# NBT_UIO_INT.net
KiCad netlist of a schematic drawn in Altium Designer
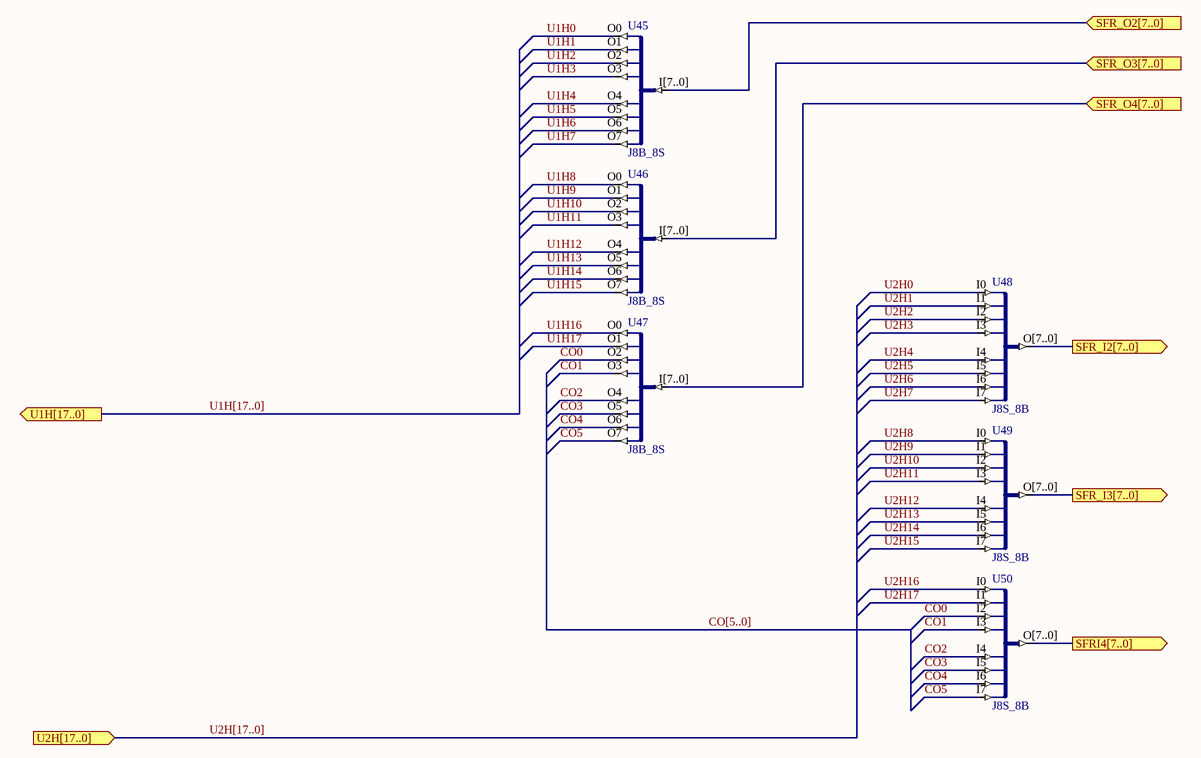
[diagram p0: NBT_UIO_INT.SCHDOC]

(export (version "E")
  (design (tool "Eeschema 10.0.6"))
  (components
    (comp (ref "U45")
      (value "J8B_8S")
      (description "8-Bit input bus to 8 single pin outputs")
      (fields (field (name "PUBLISHER") "Altium Limited"))
      (libsource (lib "FPGA Generic") (part "J8B_8S"))
    )
    (comp (ref "U46")
      (value "J8B_8S")
      (description "8-Bit input bus to 8 single pin outputs")
      (fields (field (name "PUBLISHER") "Altium Limited"))
      (libsource (lib "FPGA Generic") (part "J8B_8S"))
    )
    (comp (ref "U47")
      (value "J8B_8S")
      (description "8-Bit input bus to 8 single pin outputs")
      (fields (field (name "PUBLISHER") "Altium Limited"))
      (libsource (lib "FPGA Generic") (part "J8B_8S"))
    )
    (comp (ref "U48")
      (value "J8S_8B")
      (description "8 Single pin inputs to single 8-Bit output bus")
      (fields (field (name "PUBLISHER") "Altium Limited"))
      (libsource (lib "FPGA Generic") (part "J8S_8B"))
    )
    (comp (ref "U49")
      (value "J8S_8B")
      (description "8 Single pin inputs to single 8-Bit output bus")
      (fields (field (name "PUBLISHER") "Altium Limited"))
      (libsource (lib "FPGA Generic") (part "J8S_8B"))
    )
    (comp (ref "U50")
      (value "J8S_8B")
      (description "8 Single pin inputs to single 8-Bit output bus")
      (fields (field (name "PUBLISHER") "Altium Limited"))
      (libsource (lib "FPGA Generic") (part "J8S_8B"))
    )
  )
  (nets
    (net (code "49") (name "/CO0") (class "Default")
      (node (ref "U47") (pin "O2") (pinfunction "O2_O2") (pintype "output"))
      (node (ref "U50") (pin "I2") (pinfunction "I2_I2") (pintype "input"))
    )
    (net (code "50") (name "/CO1") (class "Default")
      (node (ref "U47") (pin "O3") (pinfunction "O3_O3") (pintype "output"))
      (node (ref "U50") (pin "I3") (pinfunction "I3_I3") (pintype "input"))
    )
    (net (code "51") (name "/CO2") (class "Default")
      (node (ref "U47") (pin "O4") (pinfunction "O4_O4") (pintype "output"))
      (node (ref "U50") (pin "I4") (pinfunction "I4_I4") (pintype "input"))
    )
    (net (code "52") (name "/CO3") (class "Default")
      (node (ref "U47") (pin "O5") (pinfunction "O5_O5") (pintype "output"))
      (node (ref "U50") (pin "I5") (pinfunction "I5_I5") (pintype "input"))
    )
    (net (code "53") (name "/CO4") (class "Default")
      (node (ref "U47") (pin "O6") (pinfunction "O6_O6") (pintype "output"))
      (node (ref "U50") (pin "I6") (pinfunction "I6_I6") (pintype "input"))
    )
    (net (code "54") (name "/CO5") (class "Default")
      (node (ref "U47") (pin "O7") (pinfunction "O7_O7") (pintype "output"))
      (node (ref "U50") (pin "I7") (pinfunction "I7_I7") (pintype "input"))
    )
    (net (code "56") (name "/SFRI4[7..0]") (class "Default")
      (node (ref "U50") (pin "O[7..0]") (pinfunction "O[7..0]_O[7..0]") (pintype "output"))
    )
    (net (code "57") (name "/SFR_I2[7..0]") (class "Default")
      (node (ref "U48") (pin "O[7..0]") (pinfunction "O[7..0]_O[7..0]") (pintype "output"))
    )
    (net (code "58") (name "/SFR_I3[7..0]") (class "Default")
      (node (ref "U49") (pin "O[7..0]") (pinfunction "O[7..0]_O[7..0]") (pintype "output"))
    )
    (net (code "59") (name "/SFR_O2[7..0]") (class "Default")
      (node (ref "U45") (pin "I[7..0]") (pinfunction "I[7..0]_I[7..0]") (pintype "input"))
    )
    (net (code "60") (name "/SFR_O3[7..0]") (class "Default")
      (node (ref "U46") (pin "I[7..0]") (pinfunction "I[7..0]_I[7..0]") (pintype "input"))
    )
    (net (code "61") (name "/SFR_O4[7..0]") (class "Default")
      (node (ref "U47") (pin "I[7..0]") (pinfunction "I[7..0]_I[7..0]") (pintype "input"))
    )
    (net (code "62") (name "/U1H0") (class "Default")
      (node (ref "U45") (pin "O0") (pinfunction "O0_O0") (pintype "output"))
    )
    (net (code "63") (name "/U1H1") (class "Default")
      (node (ref "U45") (pin "O1") (pinfunction "O1_O1") (pintype "output"))
    )
    (net (code "64") (name "/U1H2") (class "Default")
      (node (ref "U45") (pin "O2") (pinfunction "O2_O2") (pintype "output"))
    )
    (net (code "65") (name "/U1H3") (class "Default")
      (node (ref "U45") (pin "O3") (pinfunction "O3_O3") (pintype "output"))
    )
    (net (code "66") (name "/U1H4") (class "Default")
      (node (ref "U45") (pin "O4") (pinfunction "O4_O4") (pintype "output"))
    )
    (net (code "67") (name "/U1H5") (class "Default")
      (node (ref "U45") (pin "O5") (pinfunction "O5_O5") (pintype "output"))
    )
    (net (code "68") (name "/U1H6") (class "Default")
      (node (ref "U45") (pin "O6") (pinfunction "O6_O6") (pintype "output"))
    )
    (net (code "69") (name "/U1H7") (class "Default")
      (node (ref "U45") (pin "O7") (pinfunction "O7_O7") (pintype "output"))
    )
    (net (code "70") (name "/U1H8") (class "Default")
      (node (ref "U46") (pin "O0") (pinfunction "O0_O0") (pintype "output"))
    )
    (net (code "71") (name "/U1H9") (class "Default")
      (node (ref "U46") (pin "O1") (pinfunction "O1_O1") (pintype "output"))
    )
    (net (code "72") (name "/U1H10") (class "Default")
      (node (ref "U46") (pin "O2") (pinfunction "O2_O2") (pintype "output"))
    )
    (net (code "73") (name "/U1H11") (class "Default")
      (node (ref "U46") (pin "O3") (pinfunction "O3_O3") (pintype "output"))
    )
    (net (code "74") (name "/U1H12") (class "Default")
      (node (ref "U46") (pin "O4") (pinfunction "O4_O4") (pintype "output"))
    )
    (net (code "75") (name "/U1H13") (class "Default")
      (node (ref "U46") (pin "O5") (pinfunction "O5_O5") (pintype "output"))
    )
    (net (code "76") (name "/U1H14") (class "Default")
      (node (ref "U46") (pin "O6") (pinfunction "O6_O6") (pintype "output"))
    )
    (net (code "77") (name "/U1H15") (class "Default")
      (node (ref "U46") (pin "O7") (pinfunction "O7_O7") (pintype "output"))
    )
    (net (code "78") (name "/U1H16") (class "Default")
      (node (ref "U47") (pin "O0") (pinfunction "O0_O0") (pintype "output"))
    )
    (net (code "79") (name "/U1H17") (class "Default")
      (node (ref "U47") (pin "O1") (pinfunction "O1_O1") (pintype "output"))
    )
    (net (code "81") (name "/U2H0") (class "Default")
      (node (ref "U48") (pin "I0") (pinfunction "I0_I0") (pintype "input"))
    )
    (net (code "82") (name "/U2H1") (class "Default")
      (node (ref "U48") (pin "I1") (pinfunction "I1_I1") (pintype "input"))
    )
    (net (code "83") (name "/U2H2") (class "Default")
      (node (ref "U48") (pin "I2") (pinfunction "I2_I2") (pintype "input"))
    )
    (net (code "84") (name "/U2H3") (class "Default")
      (node (ref "U48") (pin "I3") (pinfunction "I3_I3") (pintype "input"))
    )
    (net (code "85") (name "/U2H4") (class "Default")
      (node (ref "U48") (pin "I4") (pinfunction "I4_I4") (pintype "input"))
    )
    (net (code "86") (name "/U2H5") (class "Default")
      (node (ref "U48") (pin "I5") (pinfunction "I5_I5") (pintype "input"))
    )
    (net (code "87") (name "/U2H6") (class "Default")
      (node (ref "U48") (pin "I6") (pinfunction "I6_I6") (pintype "input"))
    )
    (net (code "88") (name "/U2H7") (class "Default")
      (node (ref "U48") (pin "I7") (pinfunction "I7_I7") (pintype "input"))
    )
    (net (code "89") (name "/U2H8") (class "Default")
      (node (ref "U49") (pin "I0") (pinfunction "I0_I0") (pintype "input"))
    )
    (net (code "90") (name "/U2H9") (class "Default")
      (node (ref "U49") (pin "I1") (pinfunction "I1_I1") (pintype "input"))
    )
    (net (code "91") (name "/U2H10") (class "Default")
      (node (ref "U49") (pin "I2") (pinfunction "I2_I2") (pintype "input"))
    )
    (net (code "92") (name "/U2H11") (class "Default")
      (node (ref "U49") (pin "I3") (pinfunction "I3_I3") (pintype "input"))
    )
    (net (code "93") (name "/U2H12") (class "Default")
      (node (ref "U49") (pin "I4") (pinfunction "I4_I4") (pintype "input"))
    )
    (net (code "94") (name "/U2H13") (class "Default")
      (node (ref "U49") (pin "I5") (pinfunction "I5_I5") (pintype "input"))
    )
    (net (code "95") (name "/U2H14") (class "Default")
      (node (ref "U49") (pin "I6") (pinfunction "I6_I6") (pintype "input"))
    )
    (net (code "96") (name "/U2H15") (class "Default")
      (node (ref "U49") (pin "I7") (pinfunction "I7_I7") (pintype "input"))
    )
    (net (code "97") (name "/U2H16") (class "Default")
      (node (ref "U50") (pin "I0") (pinfunction "I0_I0") (pintype "input"))
    )
    (net (code "98") (name "/U2H17") (class "Default")
      (node (ref "U50") (pin "I1") (pinfunction "I1_I1") (pintype "input"))
    )
  )
)
